# parakeet_board_rev_07.net
KiCad netlist of a schematic drawn in EAGLE
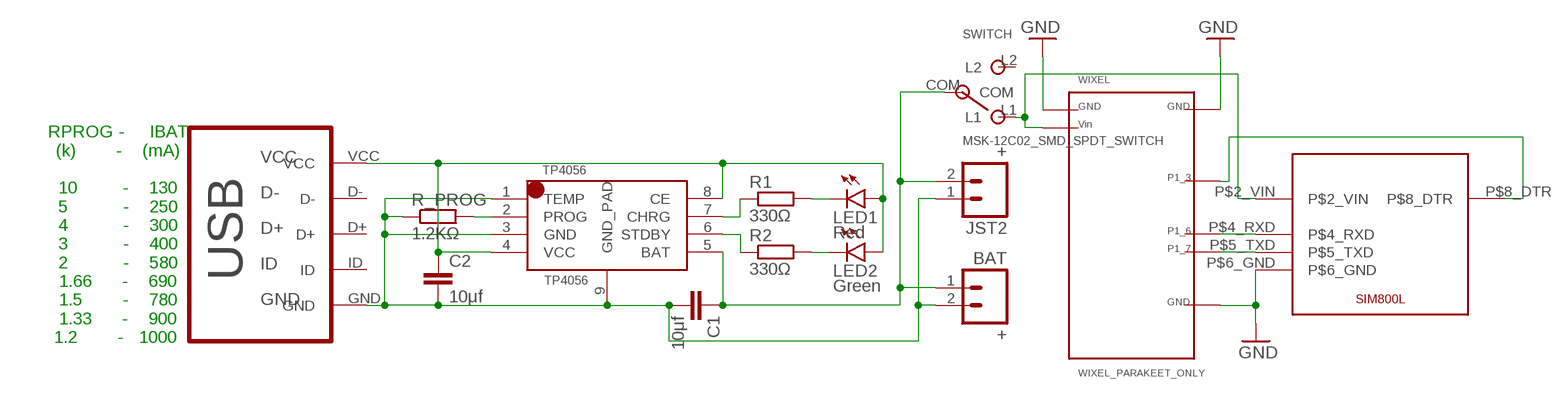
[diagram p0: schematic, sheet 1]

(export (version "E")
  (design (tool "Eeschema 10.0.6"))
  (components
    (comp (ref "+")
      (value "BAT")
      (footprint "eagle-import:1X02")
      (libsource (lib "eagle-import") (part "M02PTH"))
    )
    (comp (ref "C1")
      (value "10μf")
      (footprint "eagle-import:C1206")
      (libsource (lib "eagle-import") (part "C-EUC1206"))
    )
    (comp (ref "C2")
      (value "10μf")
      (footprint "eagle-import:C1206")
      (libsource (lib "eagle-import") (part "C-EUC1206"))
    )
    (comp (ref "JST2")
      (value "+")
      (footprint "eagle-import:JST-2-SMD")
      (libsource (lib "eagle-import") (part "M02-JST-2MM-SMT"))
    )
    (comp (ref "LED1")
      (value "Red")
      (footprint "eagle-import:LED-1206")
      (libsource (lib "eagle-import") (part "LED1206"))
    )
    (comp (ref "LED2")
      (value "Green")
      (footprint "eagle-import:LED-1206")
      (libsource (lib "eagle-import") (part "LED1206"))
    )
    (comp (ref "R1")
      (value "330Ω")
      (footprint "eagle-import:R1206")
      (libsource (lib "eagle-import") (part "R-EU_R1206"))
    )
    (comp (ref "R2")
      (value "330Ω")
      (footprint "eagle-import:R1206")
      (libsource (lib "eagle-import") (part "R-EU_R1206"))
    )
    (comp (ref "R_PROG")
      (value "1.2KΩ")
      (footprint "eagle-import:R1206")
      (libsource (lib "eagle-import") (part "R-EU_R1206"))
    )
    (comp (ref "SIM800L")
      (value "SIM800L_PARAKEET_ONLY")
      (footprint "eagle-import:SIM800L_PARAKEET_ONLY")
      (libsource (lib "eagle-import") (part "SIM800L_PARAKEET_ONLY"))
    )
    (comp (ref "SWITCH")
      (value "MSK-12C02_SMD_SPDT_SWITCH")
      (footprint "eagle-import:MSK-12C02")
      (libsource (lib "eagle-import") (part "MSK-12C02_SMD_SPDT_SWITCH"))
    )
    (comp (ref "TP4056")
      (value "TP4056")
      (footprint "eagle-import:SOP-8")
      (libsource (lib "eagle-import") (part "TP4056"))
    )
    (comp (ref "USB")
      (value "MICRO-USB-B")
      (footprint "eagle-import:MICRO_USB_4_LEGS")
      (libsource (lib "eagle-import") (part "MICRO-USB-B"))
    )
    (comp (ref "WIXEL")
      (value "WIXEL_PARAKEET_ONLY")
      (footprint "eagle-import:WIXEL_PARAKEET_ONLY")
      (libsource (lib "eagle-import") (part "WIXEL_PARAKEET_ONLY"))
    )
  )
  (nets
    (net (code "1") (name "GND") (class "Default")
      (node (ref "+") (pin "2") (pinfunction "2_2") (pintype "passive"))
      (node (ref "C1") (pin "2") (pinfunction "2_2") (pintype "passive"))
      (node (ref "C2") (pin "2") (pinfunction "2_2") (pintype "passive"))
      (node (ref "JST2") (pin "1") (pinfunction "2_1") (pintype "passive"))
      (node (ref "R_PROG") (pin "1") (pinfunction "1_1") (pintype "passive"))
      (node (ref "SIM800L") (pin "P$6_GND") (pinfunction "P$6_GND_P$6_GND") (pintype "bidirectional"))
      (node (ref "TP4056") (pin "1") (pinfunction "TEMP_1") (pintype "bidirectional"))
      (node (ref "TP4056") (pin "3") (pinfunction "GND_3") (pintype "bidirectional"))
      (node (ref "TP4056") (pin "9") (pinfunction "GND_PAD_9") (pintype "bidirectional"))
      (node (ref "USB") (pin "GND") (pinfunction "GND_GND") (pintype "bidirectional"))
      (node (ref "WIXEL") (pin "P$1") (pinfunction "P$1-GND1_P$1") (pintype "bidirectional"))
      (node (ref "WIXEL") (pin "P$12") (pinfunction "P$12-GND2_P$12") (pintype "bidirectional"))
      (node (ref "WIXEL") (pin "P$23") (pinfunction "P$23-GND3_P$23") (pintype "bidirectional"))
    )
    (net (code "2") (name "Net-(JST2-1)") (class "Default")
      (node (ref "+") (pin "1") (pinfunction "1_1") (pintype "passive"))
      (node (ref "C1") (pin "1") (pinfunction "1_1") (pintype "passive"))
      (node (ref "JST2") (pin "2") (pinfunction "1_2") (pintype "passive"))
      (node (ref "SWITCH") (pin "COM") (pinfunction "COM_COM") (pintype "bidirectional"))
      (node (ref "TP4056") (pin "5") (pinfunction "BAT_5") (pintype "bidirectional"))
    )
    (net (code "3") (name "Net-(LED1-PadC)") (class "Default")
      (node (ref "LED1") (pin "C") (pinfunction "C_C") (pintype "passive"))
      (node (ref "R1") (pin "2") (pinfunction "2_2") (pintype "passive"))
    )
    (net (code "4") (name "Net-(LED2-PadC)") (class "Default")
      (node (ref "LED2") (pin "C") (pinfunction "C_C") (pintype "passive"))
      (node (ref "R2") (pin "2") (pinfunction "2_2") (pintype "passive"))
    )
    (net (code "5") (name "Net-(TP4056-CE)") (class "Default")
      (node (ref "C2") (pin "1") (pinfunction "1_1") (pintype "passive"))
      (node (ref "LED1") (pin "A") (pinfunction "A_A") (pintype "passive"))
      (node (ref "LED2") (pin "A") (pinfunction "A_A") (pintype "passive"))
      (node (ref "TP4056") (pin "4") (pinfunction "VCC_4") (pintype "bidirectional"))
      (node (ref "TP4056") (pin "8") (pinfunction "CE_8") (pintype "bidirectional"))
      (node (ref "USB") (pin "VCC") (pinfunction "VCC_VCC") (pintype "bidirectional"))
    )
    (net (code "6") (name "Net-(TP4056-CHRG)") (class "Default")
      (node (ref "R1") (pin "1") (pinfunction "1_1") (pintype "passive"))
      (node (ref "TP4056") (pin "7") (pinfunction "CHRG_7") (pintype "bidirectional"))
    )
    (net (code "7") (name "Net-(TP4056-PROG)") (class "Default")
      (node (ref "R_PROG") (pin "2") (pinfunction "2_2") (pintype "passive"))
      (node (ref "TP4056") (pin "2") (pinfunction "PROG_2") (pintype "bidirectional"))
    )
    (net (code "8") (name "Net-(TP4056-STDBY)") (class "Default")
      (node (ref "R2") (pin "1") (pinfunction "1_1") (pintype "passive"))
      (node (ref "TP4056") (pin "6") (pinfunction "STDBY_6") (pintype "bidirectional"))
    )
    (net (code "9") (name "Net-(WIXEL-P$2-VIN)") (class "Default")
      (node (ref "SIM800L") (pin "P$2_VIN") (pinfunction "P$2_VIN_P$2_VIN") (pintype "bidirectional"))
      (node (ref "SWITCH") (pin "L1") (pinfunction "L1_L1") (pintype "bidirectional"))
      (node (ref "WIXEL") (pin "P$2") (pinfunction "P$2-VIN_P$2") (pintype "bidirectional"))
    )
    (net (code "10") (name "Net-(WIXEL-P$16-P1_3)") (class "Default")
      (node (ref "SIM800L") (pin "P$8_DTR") (pinfunction "P$8_DTR_P$8_DTR") (pintype "bidirectional"))
      (node (ref "WIXEL") (pin "P$16") (pinfunction "P$16-P1_3_P$16") (pintype "bidirectional"))
    )
    (net (code "11") (name "Net-(WIXEL-P$19-P1_6)") (class "Default")
      (node (ref "SIM800L") (pin "P$4_RXD") (pinfunction "P$4_RXD_P$4_RXD") (pintype "bidirectional"))
      (node (ref "WIXEL") (pin "P$19") (pinfunction "P$19-P1_6_P$19") (pintype "bidirectional"))
    )
    (net (code "12") (name "Net-(WIXEL-P$20-P1_7)") (class "Default")
      (node (ref "SIM800L") (pin "P$5_TXD") (pinfunction "P$5_TXD_P$5_TXD") (pintype "bidirectional"))
      (node (ref "WIXEL") (pin "P$20") (pinfunction "P$20-P1_7_P$20") (pintype "bidirectional"))
    )
    (net (code "13") (name "unconnected-(SWITCH-PadL2)") (class "Default")
      (node (ref "SWITCH") (pin "L2") (pinfunction "L2_L2") (pintype "bidirectional"))
    )
    (net (code "14") (name "unconnected-(USB-PadD+)") (class "Default")
      (node (ref "USB") (pin "D+") (pinfunction "D+_D+") (pintype "bidirectional"))
    )
    (net (code "15") (name "unconnected-(USB-PadD-)") (class "Default")
      (node (ref "USB") (pin "D-") (pinfunction "D-_D-") (pintype "bidirectional"))
    )
    (net (code "16") (name "unconnected-(USB-PadID)") (class "Default")
      (node (ref "USB") (pin "ID") (pinfunction "ID_ID") (pintype "bidirectional"))
    )
  )
)
